# Motor_Power_Switch.net
KiCad netlist of a schematic drawn in Altium Designer
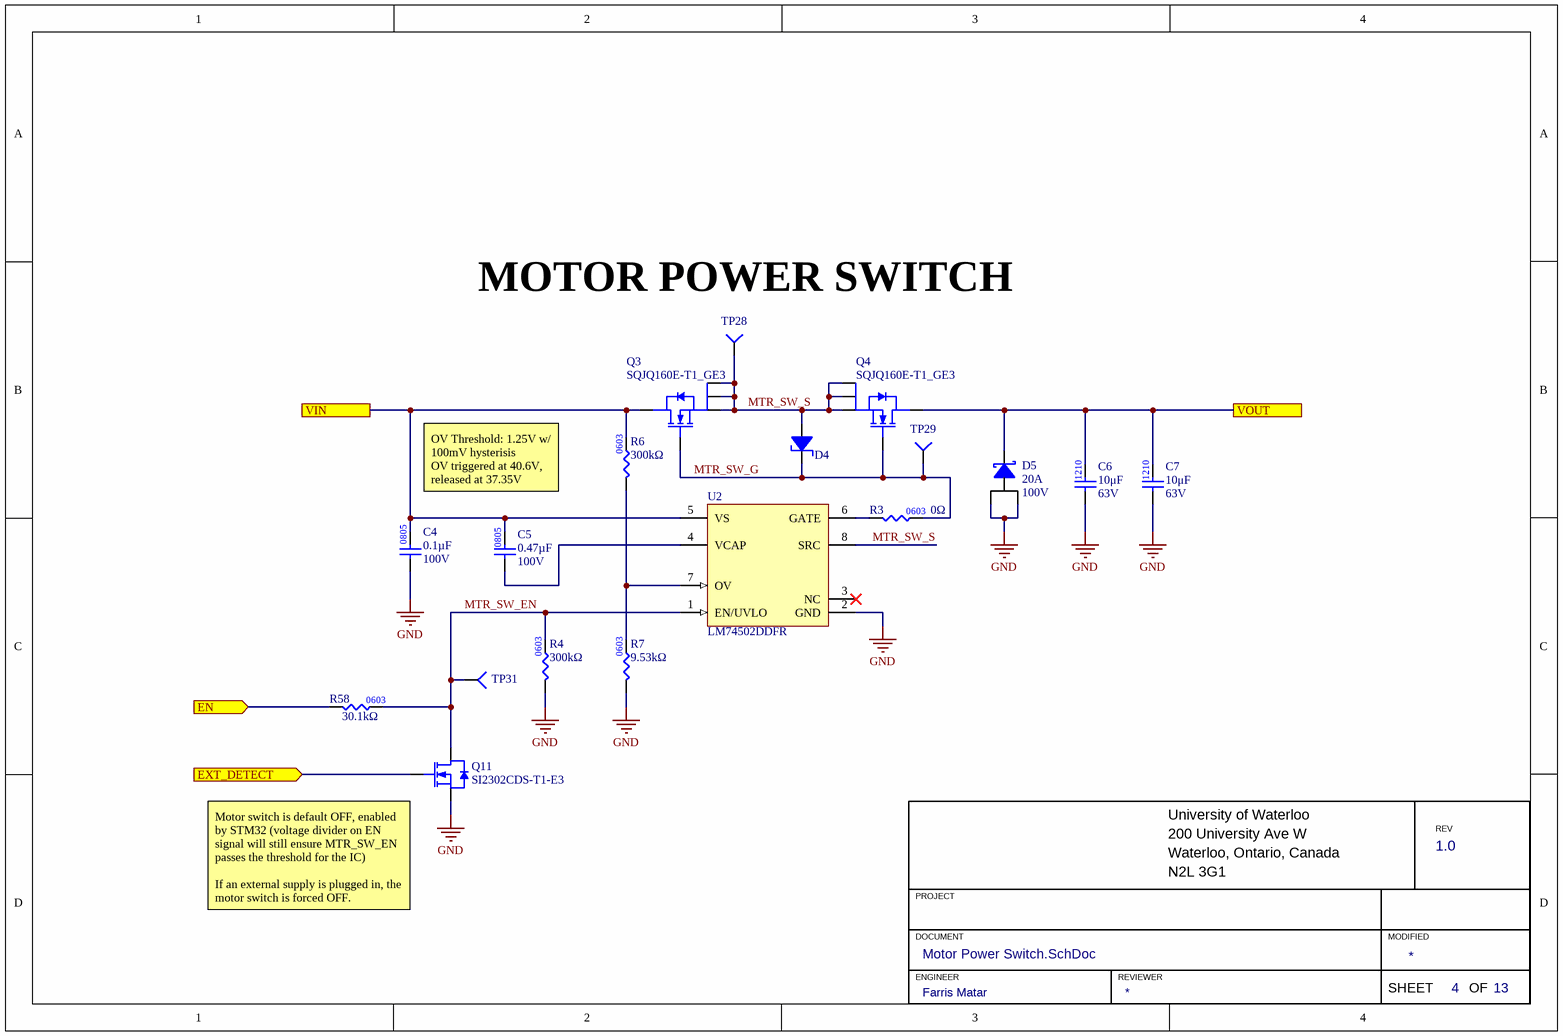
[diagram p0: Motor Power Switch.SchDoc]

(export (version "E")
  (design (tool "Eeschema 10.0.6"))
  (components
    (comp (ref "C4")
      (value "0.1µF")
      (footprint "CAP0805")
      (description "CAP CER 0.1UF 100V X7R 0805")
      (fields (field (name "VOLTAGE RATING") "100V") (field (name "Comment") "CAP_0.1uF_100V_0805"))
      (libsource (lib "Personal_Schematic_Library_2022") (part "CAP_0.1uF_100V_0805"))
    )
    (comp (ref "C5")
      (value "0.47µF")
      (footprint "CAP0805")
      (description "CAP CER 0.47UF 100V X7R 0805")
      (fields (field (name "VOLTAGE RATING") "100V") (field (name "Comment") "CAP_0.47uF_100V_0805"))
      (libsource (lib "Personal_Schematic_Library_2022") (part "CAP_0.47uF_100V_0805"))
    )
    (comp (ref "C6")
      (value "10μF")
      (footprint "CAP1210")
      (description "CAP CER 10UF 63V X7R 1210")
      (fields (field (name "VOLTAGE RATING") "63V") (field (name "Comment") "CAP_10uF_63V_1210"))
      (libsource (lib "Personal_Schematic_Library_2022") (part "CAP_10uF_63V_1210"))
    )
    (comp (ref "C7")
      (value "10μF")
      (footprint "CAP1210")
      (description "CAP CER 10UF 63V X7R 1210")
      (fields (field (name "VOLTAGE RATING") "63V") (field (name "Comment") "CAP_10uF_63V_1210"))
      (libsource (lib "Personal_Schematic_Library_2022") (part "CAP_10uF_63V_1210"))
    )
    (comp (ref "D4")
      (value "DIO_ZENER_16V")
      (footprint "SOD-123_FLAT")
      (description "DIODE ZENER 16V 500MW SOD123")
      (libsource (lib "Personal_Schematic_Library_2022") (part "DIO_ZENER_16V"))
    )
    (comp (ref "D5")
      (value "DIO_SCHOTTKY_100V_20A")
      (footprint "D-PAK")
      (description "100V, 20A, DPAK, DIODE SCHOTTKY")
      (fields (field (name "CURRENT - AVERAGE RECTIFIED (IO)") "20A") (field (name "VR (MAX)") "100V"))
      (libsource (lib "Personal_Schematic_Library_2022") (part "DIO_SCHOTTKY_100V_20A"))
    )
    (comp (ref "Q3")
      (value "NMOS_60V_603A")
      (footprint "VISHAY_PowerPAK-8x8")
      (description "AUTOMOTIVE N-CHANNEL 60 V (D-S)")
      (fields (field (name "MANUFACTURER PART NUMBER 1") "SQJQ160E-T1_GE3"))
      (libsource (lib "Personal_Schematic_Library_2022") (part "NMOS_60V_603A"))
    )
    (comp (ref "Q4")
      (value "NMOS_60V_603A")
      (footprint "VISHAY_PowerPAK-8x8")
      (description "AUTOMOTIVE N-CHANNEL 60 V (D-S)")
      (fields (field (name "MANUFACTURER PART NUMBER 1") "SQJQ160E-T1_GE3"))
      (libsource (lib "Personal_Schematic_Library_2022") (part "NMOS_60V_603A"))
    )
    (comp (ref "Q11")
      (value "NMOS_20V_6A")
      (footprint "SOT23-3")
      (description "MOSFET N-CH 20V 2.6A SOT23-3")
      (fields (field (name "MANUFACTURER PART NUMBER 1") "SI2302CDS-T1-E3"))
      (libsource (lib "Personal_Schematic_Library_2022") (part "NMOS_20V_2.6A"))
    )
    (comp (ref "R3")
      (value "0Ω")
      (footprint "RES0603")
      (description "RES 0 OHM JUMPER 1/10W 0603")
      (fields (field (name "Comment") "RES_0Ω_0603"))
      (libsource (lib "Personal_Schematic_Library_2022") (part "RES_0Ω_0603"))
    )
    (comp (ref "R4")
      (value "300kΩ")
      (footprint "RES0603")
      (description "RES 300K OHM 1% 1/10W 0603")
      (fields (field (name "TOLERANCE") "1%") (field (name "Comment") "RES_300kΩ_0603_1%"))
      (libsource (lib "Personal_Schematic_Library_2022") (part "RES_300kΩ_0603_1%"))
    )
    (comp (ref "R6")
      (value "300kΩ")
      (footprint "RES0603")
      (description "RES 300K OHM 1% 1/10W 0603")
      (fields (field (name "TOLERANCE") "1%") (field (name "Comment") "RES_300kΩ_0603_1%"))
      (libsource (lib "Personal_Schematic_Library_2022") (part "RES_300kΩ_0603_1%"))
    )
    (comp (ref "R7")
      (value "9.53kΩ")
      (footprint "RES0603")
      (description "RES 9.53K OHM 1% 1/10W 0603")
      (fields (field (name "Comment") "RES_9.53kΩ_0603_1%"))
      (libsource (lib "Personal_Schematic_Library_2022") (part "RES_9.53kΩ_0603_1%"))
    )
    (comp (ref "R58")
      (value "30.1kΩ")
      (footprint "RES0603")
      (description "RES 30.1K OHM 1% 1/10W 0603")
      (fields (field (name "Comment") "RES_30.1kΩ_0603_1%"))
      (libsource (lib "Personal_Schematic_Library_2022") (part "RES_30.1kΩ_0603_1%"))
    )
    (comp (ref "TP28")
      (value "TESTPOINT_1MM_SQUARE")
      (footprint "TESTPOINT_SQUARE_1MM")
      (description "TESTPOINT 1MM SQUARE")
      (libsource (lib "Personal_Schematic_Library_2022") (part "TESTPOINT_1MM_SQUARE"))
    )
    (comp (ref "TP29")
      (value "TESTPOINT_1MM_CIRCLE")
      (footprint "TESTPOINT_CIRCLE_1MM")
      (description "TESTPOINT 1MM CIRCLE")
      (libsource (lib "Personal_Schematic_Library_2022") (part "TESTPOINT_1MM_CIRCLE"))
    )
    (comp (ref "TP31")
      (value "TESTPOINT_1MM_CIRCLE")
      (footprint "TESTPOINT_CIRCLE_1MM")
      (description "TESTPOINT 1MM CIRCLE")
      (libsource (lib "Personal_Schematic_Library_2022") (part "TESTPOINT_1MM_CIRCLE"))
    )
    (comp (ref "U2")
      (value "LM74502DDFR")
      (footprint "TI_SOT23-8")
      (description "3.2-V TO 65-V INDUSTRIAL RPP CON")
      (libsource (lib "Personal_Schematic_Library_2022") (part "LM74502DDFR"))
    )
  )
  (nets
    (net (code "1") (name "/EN") (class "Default")
      (node (ref "R58") (pin "1") (pinfunction "1_1") (pintype "passive"))
    )
    (net (code "2") (name "/EXT_DETECT") (class "Default")
      (node (ref "Q11") (pin "1") (pinfunction "GATE_1") (pintype "passive"))
    )
    (net (code "3") (name "/MTR_SW_EN") (class "Default")
      (node (ref "Q11") (pin "3") (pinfunction "DRAIN_3") (pintype "passive"))
      (node (ref "R4") (pin "2") (pinfunction "2_2") (pintype "passive"))
      (node (ref "R58") (pin "2") (pinfunction "2_2") (pintype "passive"))
      (node (ref "TP31") (pin "1") (pinfunction "=value_1") (pintype "passive"))
      (node (ref "U2") (pin "1") (pinfunction "EN/UVLO_1") (pintype "input"))
    )
    (net (code "4") (name "/MTR_SW_G") (class "Default")
      (node (ref "D4") (pin "2") (pinfunction "Cathode_2") (pintype "passive"))
      (node (ref "Q3") (pin "1") (pinfunction "Gate_1") (pintype "passive"))
      (node (ref "Q4") (pin "1") (pinfunction "Gate_1") (pintype "passive"))
      (node (ref "R3") (pin "2") (pinfunction "2_2") (pintype "passive"))
      (node (ref "TP29") (pin "1") (pinfunction "=value_1") (pintype "passive"))
    )
    (net (code "5") (name "/MTR_SW_S") (class "Default")
      (node (ref "D4") (pin "1") (pinfunction "Anode_1") (pintype "passive"))
      (node (ref "Q3") (pin "2") (pinfunction "Source_2") (pintype "passive"))
      (node (ref "Q3") (pin "3") (pinfunction "Source_3") (pintype "passive"))
      (node (ref "Q3") (pin "4") (pinfunction "Source_4") (pintype "passive"))
      (node (ref "Q4") (pin "2") (pinfunction "Source_2") (pintype "passive"))
      (node (ref "Q4") (pin "3") (pinfunction "Source_3") (pintype "passive"))
      (node (ref "Q4") (pin "4") (pinfunction "Source_4") (pintype "passive"))
      (node (ref "TP28") (pin "1") (pinfunction "=value_1") (pintype "passive"))
      (node (ref "U2") (pin "8") (pinfunction "SRC_8") (pintype "power_in"))
    )
    (net (code "6") (name "/VIN") (class "Default")
      (node (ref "C4") (pin "2") (pinfunction "2_2") (pintype "passive"))
      (node (ref "C5") (pin "2") (pinfunction "2_2") (pintype "passive"))
      (node (ref "Q3") (pin "5") (pinfunction "Drain_5") (pintype "passive"))
      (node (ref "R6") (pin "2") (pinfunction "2_2") (pintype "passive"))
      (node (ref "U2") (pin "5") (pinfunction "VS_5") (pintype "power_in"))
    )
    (net (code "7") (name "/VOUT") (class "Default")
      (node (ref "C6") (pin "2") (pinfunction "2_2") (pintype "passive"))
      (node (ref "C7") (pin "2") (pinfunction "2_2") (pintype "passive"))
      (node (ref "D5") (pin "1") (pinfunction "Cathode_1") (pintype "passive"))
      (node (ref "Q4") (pin "5") (pinfunction "Drain_5") (pintype "passive"))
    )
    (net (code "8") (name "GND") (class "Default")
      (node (ref "C4") (pin "1") (pinfunction "1_1") (pintype "passive"))
      (node (ref "C6") (pin "1") (pinfunction "1_1") (pintype "passive"))
      (node (ref "C7") (pin "1") (pinfunction "1_1") (pintype "passive"))
      (node (ref "D5") (pin "2") (pinfunction "Anode_2") (pintype "passive"))
      (node (ref "D5") (pin "3") (pinfunction "Anode_3") (pintype "passive"))
      (node (ref "Q11") (pin "2") (pinfunction "SOURCE_2") (pintype "passive"))
      (node (ref "R4") (pin "1") (pinfunction "1_1") (pintype "passive"))
      (node (ref "R7") (pin "1") (pinfunction "1_1") (pintype "passive"))
      (node (ref "U2") (pin "2") (pinfunction "GND_2") (pintype "power_in"))
    )
    (net (code "9") (name "Net-(U2-GATE)") (class "Default")
      (node (ref "R3") (pin "1") (pinfunction "1_1") (pintype "passive"))
      (node (ref "U2") (pin "6") (pinfunction "GATE_6") (pintype "power_in"))
    )
    (net (code "10") (name "Net-(U2-OV)") (class "Default")
      (node (ref "R6") (pin "1") (pinfunction "1_1") (pintype "passive"))
      (node (ref "R7") (pin "2") (pinfunction "2_2") (pintype "passive"))
      (node (ref "U2") (pin "7") (pinfunction "OV_7") (pintype "input"))
    )
    (net (code "11") (name "Net-(U2-VCAP)") (class "Default")
      (node (ref "C5") (pin "1") (pinfunction "1_1") (pintype "passive"))
      (node (ref "U2") (pin "4") (pinfunction "VCAP_4") (pintype "power_in"))
    )
    (net (code "12") (name "unconnected-(U2-NC-Pad3)") (class "Default")
      (node (ref "U2") (pin "3") (pinfunction "NC_3") (pintype "passive+no_connect"))
    )
  )
)
